# sch_power.net
KiCad netlist of a schematic drawn in Altium Designer
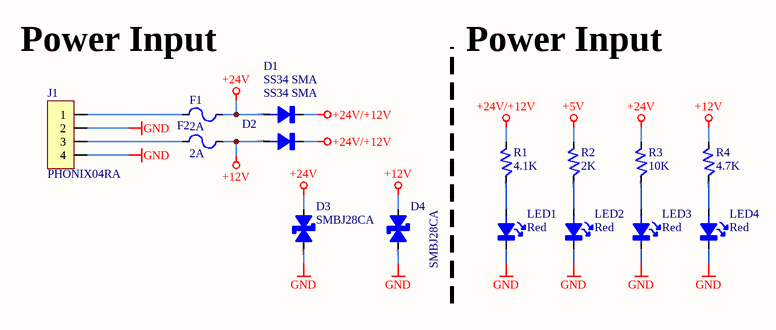
[diagram p0: sch_power.SchDoc]

(export (version "E")
  (design (tool "Eeschema 10.0.6"))
  (components
    (comp (ref "D1") (value "SS34 SMA") (footprint "SMA_diode") (libsource (lib "AliPadash") (part "DIODE")))
    (comp (ref "D2") (value "SS34 SMA") (footprint "SMA_diode") (libsource (lib "AliPadash") (part "DIODE")))
    (comp (ref "D3")
      (value "SMBJ28CA")
      (footprint "DIODEthyristors")
      (libsource (lib "AliPadash") (part "D-DIODE"))
    )
    (comp (ref "D4")
      (value "SMBJ28CA")
      (footprint "DIODEthyristors")
      (libsource (lib "AliPadash") (part "D-DIODE"))
    )
    (comp (ref "F1") (value "2A") (footprint "1206") (libsource (lib "AliPadash") (part "FUSE")))
    (comp (ref "F2") (value "2A") (footprint "1206") (libsource (lib "AliPadash") (part "FUSE")))
    (comp (ref "J1")
      (value "PHONIX04RA")
      (footprint "TER4-R-3.81")
      (libsource (lib "AliPadash") (part "CON4"))
    )
    (comp (ref "LED1") (value "Red") (footprint "0805-d") (libsource (lib "AliPadash") (part "LED")))
    (comp (ref "LED2") (value "Red") (footprint "0805-d") (libsource (lib "AliPadash") (part "LED")))
    (comp (ref "LED3") (value "Red") (footprint "0805-d") (libsource (lib "AliPadash") (part "LED")))
    (comp (ref "LED4") (value "Red") (footprint "0805-d") (libsource (lib "AliPadash") (part "LED")))
    (comp (ref "R1") (value "4.1K") (footprint "0805") (libsource (lib "AliPadash") (part "RESISTOR")))
    (comp (ref "R2") (value "2K") (footprint "0805") (libsource (lib "AliPadash") (part "RESISTOR")))
    (comp (ref "R3") (value "10K") (footprint "0805") (libsource (lib "AliPadash") (part "RESISTOR")))
    (comp (ref "R4") (value "4.7K") (footprint "0805") (libsource (lib "AliPadash") (part "RESISTOR")))
  )
  (nets
    (net (code "1") (name "+5V") (class "Default")
      (node (ref "R2") (pin "2") (pinfunction "2_2") (pintype "passive"))
    )
    (net (code "2") (name "+12V") (class "Default")
      (node (ref "D2") (pin "A") (pintype "passive"))
      (node (ref "D4") (pin "K") (pintype "passive"))
      (node (ref "F2") (pin "1") (pinfunction "1_1") (pintype "passive"))
      (node (ref "R4") (pin "2") (pinfunction "2_2") (pintype "passive"))
    )
    (net (code "3") (name "+24V") (class "Default")
      (node (ref "D1") (pin "A") (pintype "passive"))
      (node (ref "D3") (pin "K") (pintype "passive"))
      (node (ref "F1") (pin "1") (pinfunction "1_1") (pintype "passive"))
      (node (ref "R3") (pin "2") (pinfunction "2_2") (pintype "passive"))
    )
    (net (code "4") (name "+24V{slash}+12V") (class "Default")
      (node (ref "D1") (pin "K") (pintype "passive"))
      (node (ref "D2") (pin "K") (pintype "passive"))
      (node (ref "R1") (pin "2") (pinfunction "2_2") (pintype "passive"))
    )
    (net (code "5") (name "GND") (class "Default")
      (node (ref "D3") (pin "A") (pintype "passive"))
      (node (ref "D4") (pin "A") (pintype "passive"))
      (node (ref "J1") (pin "2") (pinfunction "2_2") (pintype "passive"))
      (node (ref "J1") (pin "4") (pinfunction "4_4") (pintype "passive"))
      (node (ref "LED1") (pin "K") (pintype "passive"))
      (node (ref "LED2") (pin "K") (pintype "passive"))
      (node (ref "LED3") (pin "K") (pintype "passive"))
      (node (ref "LED4") (pin "K") (pintype "passive"))
    )
    (net (code "6") (name "Net-(F1-Pad2)") (class "Default")
      (node (ref "F1") (pin "2") (pinfunction "2_2") (pintype "passive"))
      (node (ref "J1") (pin "1") (pinfunction "1_1") (pintype "passive"))
    )
    (net (code "7") (name "Net-(F2-Pad2)") (class "Default")
      (node (ref "F2") (pin "2") (pinfunction "2_2") (pintype "passive"))
      (node (ref "J1") (pin "3") (pinfunction "3_3") (pintype "passive"))
    )
    (net (code "8") (name "Net-(LED1-PadA)") (class "Default")
      (node (ref "LED1") (pin "A") (pintype "passive"))
      (node (ref "R1") (pin "1") (pinfunction "1_1") (pintype "passive"))
    )
    (net (code "9") (name "Net-(LED2-PadA)") (class "Default")
      (node (ref "LED2") (pin "A") (pintype "passive"))
      (node (ref "R2") (pin "1") (pinfunction "1_1") (pintype "passive"))
    )
    (net (code "10") (name "Net-(LED3-PadA)") (class "Default")
      (node (ref "LED3") (pin "A") (pintype "passive"))
      (node (ref "R3") (pin "1") (pinfunction "1_1") (pintype "passive"))
    )
    (net (code "11") (name "Net-(LED4-PadA)") (class "Default")
      (node (ref "LED4") (pin "A") (pintype "passive"))
      (node (ref "R4") (pin "1") (pinfunction "1_1") (pintype "passive"))
    )
  )
)
